# Power_Circuit.net
KiCad netlist of a schematic drawn in Altium Designer
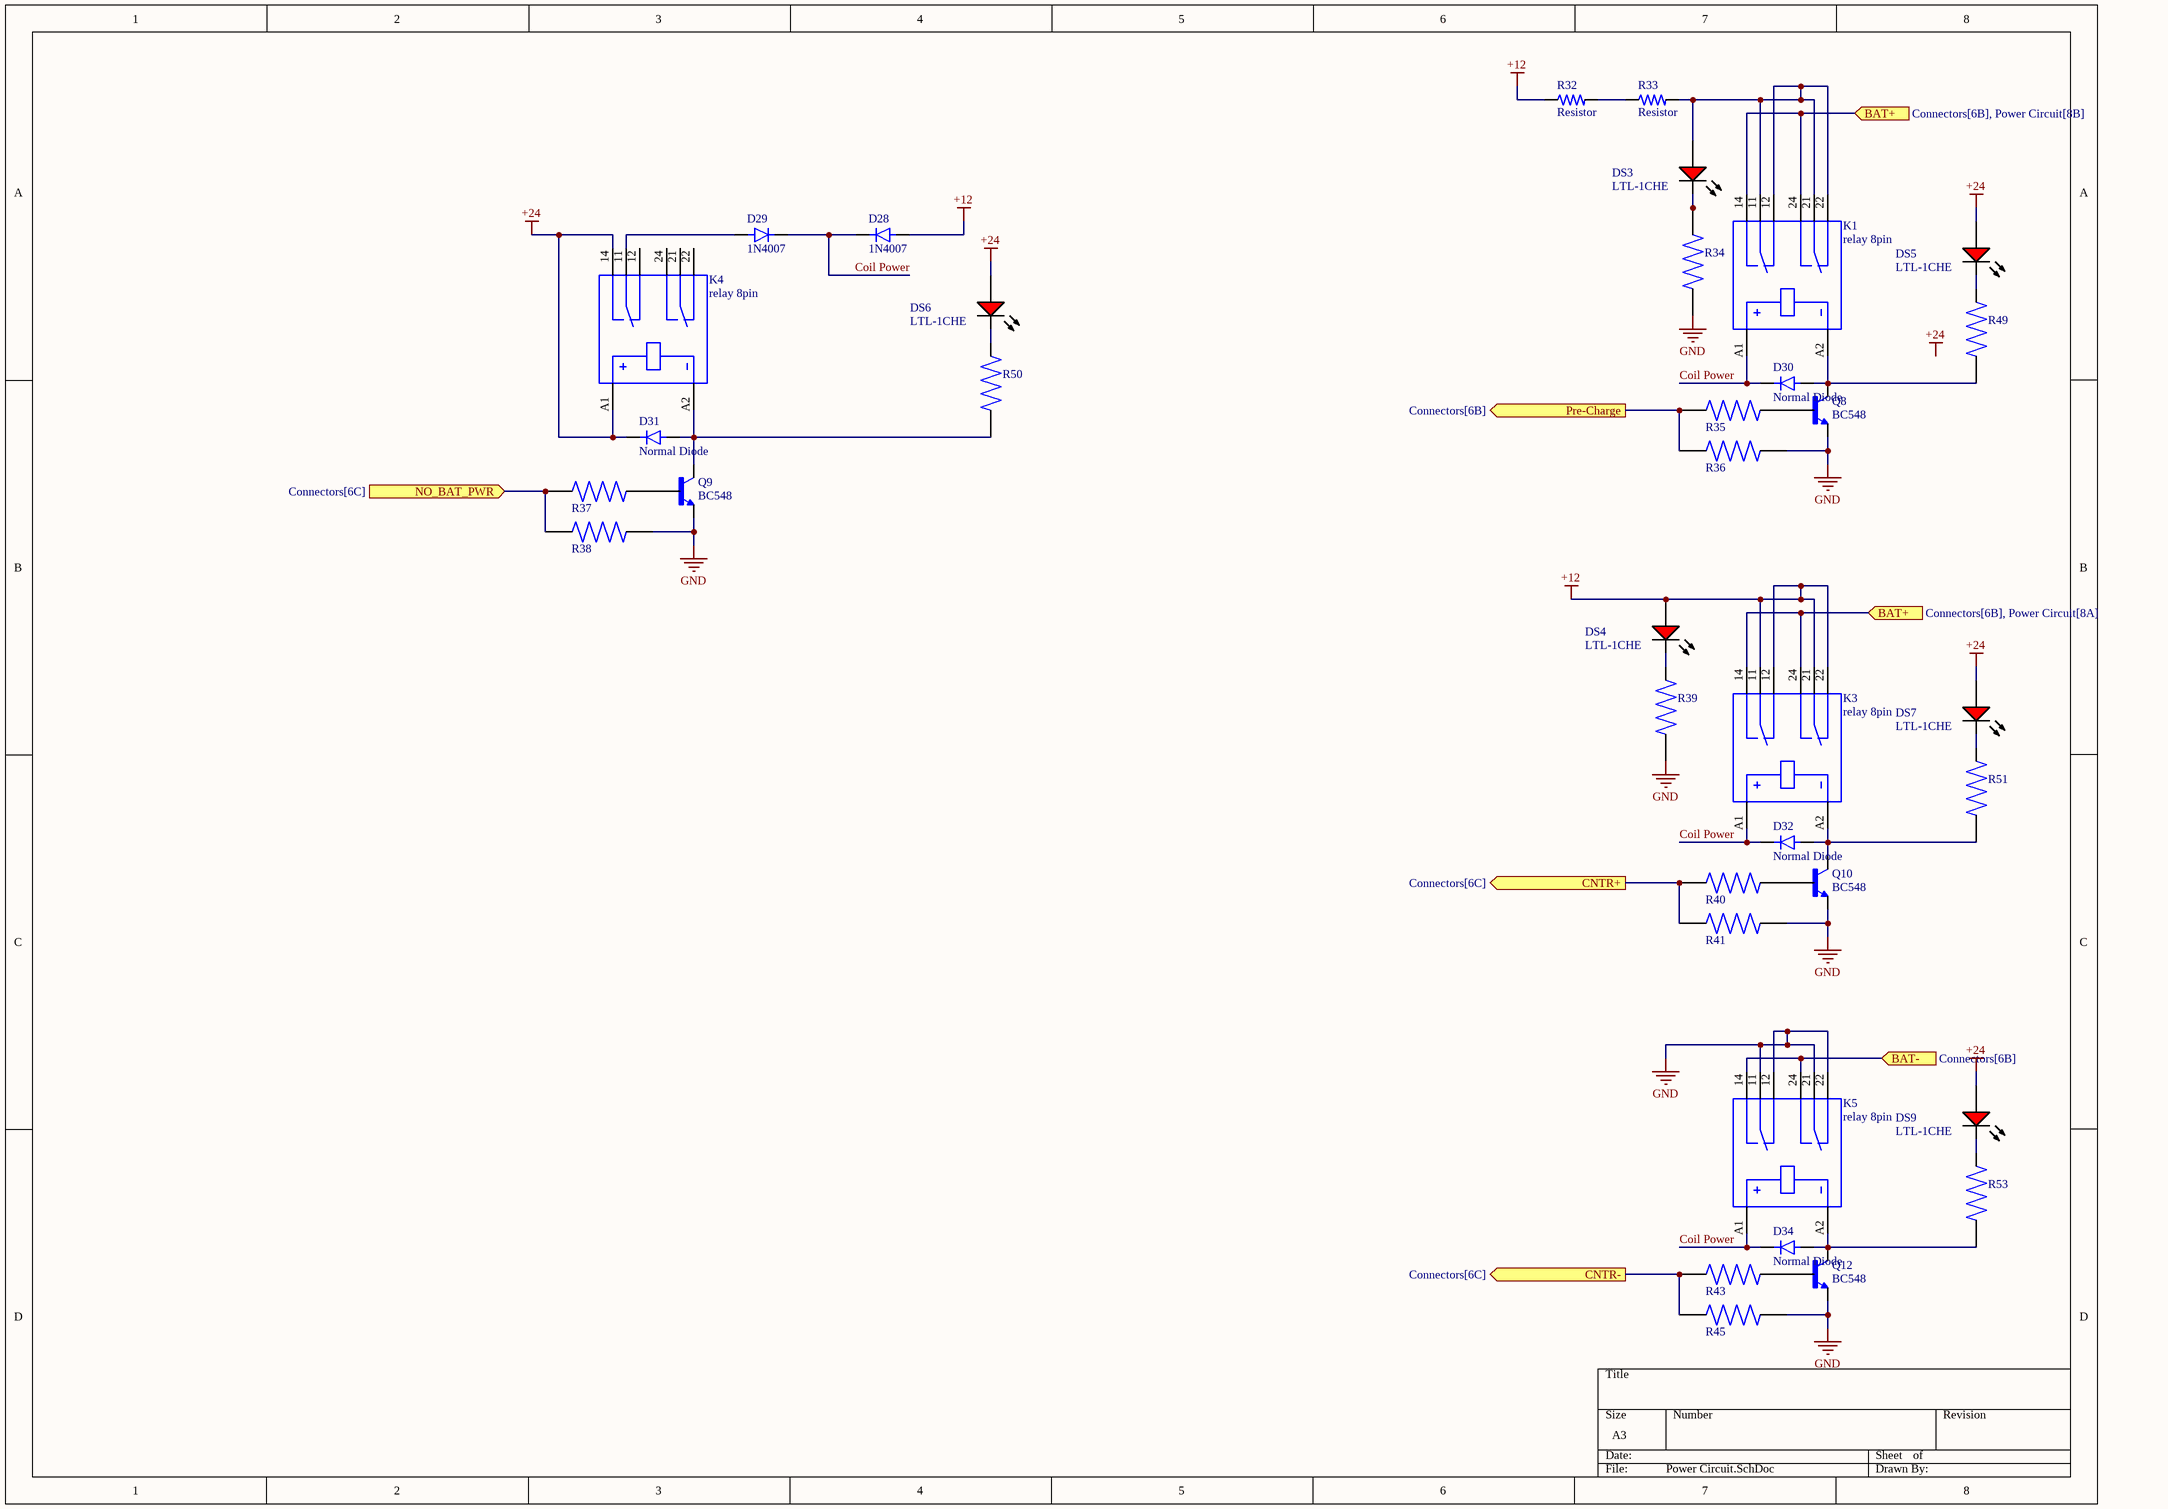
[diagram p0: Power Circuit.SchDoc]

(export (version "E")
  (design (tool "Eeschema 10.0.6"))
  (components
    (comp (ref "D28")
      (value "1N4007")
      (footprint "Common Trhough Hole")
      (fields (field (name "MF") "NTE Electronics, Inc."))
      (libsource (lib "Diodes Through Hole") (part "Normal Diode"))
    )
    (comp (ref "D29")
      (value "1N4007")
      (footprint "Common Trhough Hole")
      (fields (field (name "MF") "NTE Electronics, Inc."))
      (libsource (lib "Diodes Through Hole") (part "Normal Diode"))
    )
    (comp (ref "D30")
      (value "Normal Diode")
      (footprint "Common Trhough Hole")
      (fields (field (name "MF") "NTE Electronics, Inc.") (field (name "MP") "1N4007"))
      (libsource (lib "Diodes Through Hole") (part "Normal Diode"))
    )
    (comp (ref "D31")
      (value "Normal Diode")
      (footprint "Common Trhough Hole")
      (fields (field (name "MF") "NTE Electronics, Inc.") (field (name "MP") "1N4007"))
      (libsource (lib "Diodes Through Hole") (part "Normal Diode"))
    )
    (comp (ref "D32")
      (value "Normal Diode")
      (footprint "Common Trhough Hole")
      (fields (field (name "MF") "NTE Electronics, Inc.") (field (name "MP") "1N4007"))
      (libsource (lib "Diodes Through Hole") (part "Normal Diode"))
    )
    (comp (ref "D34")
      (value "Normal Diode")
      (footprint "Common Trhough Hole")
      (fields (field (name "MF") "NTE Electronics, Inc.") (field (name "MP") "1N4007"))
      (libsource (lib "Diodes Through Hole") (part "Normal Diode"))
    )
    (comp (ref "DS3")
      (value "LTL-1CHE")
      (footprint "LED3mm")
      (description "Radial LED, 12.6 mcd, 20 mA, 2 V, -55 to 100 degC, 2-Pin THD, RoHS, Bulk")
      (fields (field (name "TOLERANCE") "20%"))
      (libsource (lib "MySCH_Library") (part "RED_LED 3mm"))
    )
    (comp (ref "DS4")
      (value "LTL-1CHE")
      (footprint "LED3mm")
      (description "Radial LED, 12.6 mcd, 20 mA, 2 V, -55 to 100 degC, 2-Pin THD, RoHS, Bulk")
      (fields (field (name "TOLERANCE") "20%"))
      (libsource (lib "MySCH_Library") (part "RED_LED 3mm"))
    )
    (comp (ref "DS5")
      (value "LTL-1CHE")
      (footprint "LED3mm")
      (description "Radial LED, 12.6 mcd, 20 mA, 2 V, -55 to 100 degC, 2-Pin THD, RoHS, Bulk")
      (fields (field (name "TOLERANCE") "20%"))
      (libsource (lib "MySCH_Library") (part "RED_LED 3mm"))
    )
    (comp (ref "DS6")
      (value "LTL-1CHE")
      (footprint "LED3mm")
      (description "Radial LED, 12.6 mcd, 20 mA, 2 V, -55 to 100 degC, 2-Pin THD, RoHS, Bulk")
      (fields (field (name "TOLERANCE") "20%"))
      (libsource (lib "MySCH_Library") (part "RED_LED 3mm"))
    )
    (comp (ref "DS7")
      (value "LTL-1CHE")
      (footprint "LED3mm")
      (description "Radial LED, 12.6 mcd, 20 mA, 2 V, -55 to 100 degC, 2-Pin THD, RoHS, Bulk")
      (fields (field (name "TOLERANCE") "20%"))
      (libsource (lib "MySCH_Library") (part "RED_LED 3mm"))
    )
    (comp (ref "DS9")
      (value "LTL-1CHE")
      (footprint "LED3mm")
      (description "Radial LED, 12.6 mcd, 20 mA, 2 V, -55 to 100 degC, 2-Pin THD, RoHS, Bulk")
      (fields (field (name "TOLERANCE") "20%"))
      (libsource (lib "MySCH_Library") (part "RED_LED 3mm"))
    )
    (comp (ref "K1")
      (value "relay 8pin")
      (footprint "Relay socket 8pin")
      (description "General Purpose Relay DPDT _2 Form C_ 24VDC Coil Through Hole")
      (fields (field (name "MF") "TE Connectivity") (field (name "MP") "1-1393243-0"))
      (libsource (lib "MySCH_Library") (part "relay 8pin"))
    )
    (comp (ref "K3")
      (value "relay 8pin")
      (footprint "Relay socket 8pin")
      (description "General Purpose Relay DPDT _2 Form C_ 24VDC Coil Through Hole")
      (fields (field (name "MF") "TE Connectivity") (field (name "MP") "1-1393243-0"))
      (libsource (lib "MySCH_Library") (part "relay 8pin"))
    )
    (comp (ref "K4")
      (value "relay 8pin")
      (footprint "Relay socket 8pin")
      (description "General Purpose Relay DPDT _2 Form C_ 24VDC Coil Through Hole")
      (fields (field (name "MF") "TE Connectivity") (field (name "MP") "1-1393243-0"))
      (libsource (lib "MySCH_Library") (part "relay 8pin"))
    )
    (comp (ref "K5")
      (value "relay 8pin")
      (footprint "Relay socket 8pin")
      (description "General Purpose Relay DPDT _2 Form C_ 24VDC Coil Through Hole")
      (fields (field (name "MF") "TE Connectivity") (field (name "MP") "1-1393243-0"))
      (libsource (lib "MySCH_Library") (part "relay 8pin"))
    )
    (comp (ref "Q8")
      (value "BC548")
      (footprint "bc548")
      (description "Bipolar (BJT) Transistor NPN 30V 100mA 300MHz 500mW Through Hole TO-92-3")
      (fields (field (name "MF") "ON Semiconductor"))
      (libsource (lib "MySCH_Library") (part "BC548"))
    )
    (comp (ref "Q9")
      (value "BC548")
      (footprint "bc548")
      (description "Bipolar (BJT) Transistor NPN 30V 100mA 300MHz 500mW Through Hole TO-92-3")
      (fields (field (name "MF") "ON Semiconductor"))
      (libsource (lib "MySCH_Library") (part "BC548"))
    )
    (comp (ref "Q10")
      (value "BC548")
      (footprint "bc548")
      (description "Bipolar (BJT) Transistor NPN 30V 100mA 300MHz 500mW Through Hole TO-92-3")
      (fields (field (name "MF") "ON Semiconductor"))
      (libsource (lib "MySCH_Library") (part "BC548"))
    )
    (comp (ref "Q12")
      (value "BC548")
      (footprint "bc548")
      (description "Bipolar (BJT) Transistor NPN 30V 100mA 300MHz 500mW Through Hole TO-92-3")
      (fields (field (name "MF") "ON Semiconductor"))
      (libsource (lib "MySCH_Library") (part "BC548"))
    )
    (comp (ref "R32")
      (value "Resistor")
      (footprint "Resistor_Through Hole")
      (fields
        (field (name "MP") "2-2176053-0")
        (field (name "TOLERANCE") "1%")
        (field (name "MF") "TE Connectivity")
      )
      (libsource (lib "Resistors Through Hole") (part "Resistor"))
    )
    (comp (ref "R33")
      (value "Resistor")
      (footprint "Resistor_Through Hole")
      (fields
        (field (name "MP") "2-2176053-0")
        (field (name "TOLERANCE") "1%")
        (field (name "MF") "TE Connectivity")
      )
      (libsource (lib "Resistors Through Hole") (part "Resistor"))
    )
    (comp (ref "R34")
      (value "Resistor_Through Hole")
      (footprint "Resistor_Through Hole")
      (description "1.02 Ohms Â±1% 0.25W, 1/4W Through Hole Resistor Axial Metal Film")
      (fields (field (name "MP") "MFR-25FTE52-1R") (field (name "MF") "Yageo"))
      (libsource (lib "MySCH_Library") (part "Resistor_Through Hole"))
    )
    (comp (ref "R35")
      (value "Resistor_Through Hole")
      (footprint "Resistor_Through Hole")
      (description "1.02 Ohms Â±1% 0.25W, 1/4W Through Hole Resistor Axial Metal Film")
      (fields (field (name "MP") "MFR-25FTE52-1R") (field (name "MF") "Yageo"))
      (libsource (lib "MySCH_Library") (part "Resistor_Through Hole"))
    )
    (comp (ref "R36")
      (value "Resistor_Through Hole")
      (footprint "Resistor_Through Hole")
      (description "1.02 Ohms Â±1% 0.25W, 1/4W Through Hole Resistor Axial Metal Film")
      (fields (field (name "MP") "MFR-25FTE52-1R") (field (name "MF") "Yageo"))
      (libsource (lib "MySCH_Library") (part "Resistor_Through Hole"))
    )
    (comp (ref "R37")
      (value "Resistor_Through Hole")
      (footprint "Resistor_Through Hole")
      (description "1.02 Ohms Â±1% 0.25W, 1/4W Through Hole Resistor Axial Metal Film")
      (fields (field (name "MP") "MFR-25FTE52-1R") (field (name "MF") "Yageo"))
      (libsource (lib "MySCH_Library") (part "Resistor_Through Hole"))
    )
    (comp (ref "R38")
      (value "Resistor_Through Hole")
      (footprint "Resistor_Through Hole")
      (description "1.02 Ohms Â±1% 0.25W, 1/4W Through Hole Resistor Axial Metal Film")
      (fields (field (name "MP") "MFR-25FTE52-1R") (field (name "MF") "Yageo"))
      (libsource (lib "MySCH_Library") (part "Resistor_Through Hole"))
    )
    (comp (ref "R39")
      (value "Resistor_Through Hole")
      (footprint "Resistor_Through Hole")
      (description "1.02 Ohms Â±1% 0.25W, 1/4W Through Hole Resistor Axial Metal Film")
      (fields (field (name "MP") "MFR-25FTE52-1R") (field (name "MF") "Yageo"))
      (libsource (lib "MySCH_Library") (part "Resistor_Through Hole"))
    )
    (comp (ref "R40")
      (value "Resistor_Through Hole")
      (footprint "Resistor_Through Hole")
      (description "1.02 Ohms Â±1% 0.25W, 1/4W Through Hole Resistor Axial Metal Film")
      (fields (field (name "MP") "MFR-25FTE52-1R") (field (name "MF") "Yageo"))
      (libsource (lib "MySCH_Library") (part "Resistor_Through Hole"))
    )
    (comp (ref "R41")
      (value "Resistor_Through Hole")
      (footprint "Resistor_Through Hole")
      (description "1.02 Ohms Â±1% 0.25W, 1/4W Through Hole Resistor Axial Metal Film")
      (fields (field (name "MP") "MFR-25FTE52-1R") (field (name "MF") "Yageo"))
      (libsource (lib "MySCH_Library") (part "Resistor_Through Hole"))
    )
    (comp (ref "R43")
      (value "Resistor_Through Hole")
      (footprint "Resistor_Through Hole")
      (description "1.02 Ohms Â±1% 0.25W, 1/4W Through Hole Resistor Axial Metal Film")
      (fields (field (name "MP") "MFR-25FTE52-1R") (field (name "MF") "Yageo"))
      (libsource (lib "MySCH_Library") (part "Resistor_Through Hole"))
    )
    (comp (ref "R45")
      (value "Resistor_Through Hole")
      (footprint "Resistor_Through Hole")
      (description "1.02 Ohms Â±1% 0.25W, 1/4W Through Hole Resistor Axial Metal Film")
      (fields (field (name "MP") "MFR-25FTE52-1R") (field (name "MF") "Yageo"))
      (libsource (lib "MySCH_Library") (part "Resistor_Through Hole"))
    )
    (comp (ref "R49")
      (value "Resistor_Through Hole")
      (footprint "Resistor_Through Hole")
      (description "1.02 Ohms Â±1% 0.25W, 1/4W Through Hole Resistor Axial Metal Film")
      (fields (field (name "MP") "MFR-25FTE52-1R") (field (name "MF") "Yageo"))
      (libsource (lib "MySCH_Library") (part "Resistor_Through Hole"))
    )
    (comp (ref "R50")
      (value "Resistor_Through Hole")
      (footprint "Resistor_Through Hole")
      (description "1.02 Ohms Â±1% 0.25W, 1/4W Through Hole Resistor Axial Metal Film")
      (fields (field (name "MP") "MFR-25FTE52-1R") (field (name "MF") "Yageo"))
      (libsource (lib "MySCH_Library") (part "Resistor_Through Hole"))
    )
    (comp (ref "R51")
      (value "Resistor_Through Hole")
      (footprint "Resistor_Through Hole")
      (description "1.02 Ohms Â±1% 0.25W, 1/4W Through Hole Resistor Axial Metal Film")
      (fields (field (name "MP") "MFR-25FTE52-1R") (field (name "MF") "Yageo"))
      (libsource (lib "MySCH_Library") (part "Resistor_Through Hole"))
    )
    (comp (ref "R53")
      (value "Resistor_Through Hole")
      (footprint "Resistor_Through Hole")
      (description "1.02 Ohms Â±1% 0.25W, 1/4W Through Hole Resistor Axial Metal Film")
      (fields (field (name "MP") "MFR-25FTE52-1R") (field (name "MF") "Yageo"))
      (libsource (lib "MySCH_Library") (part "Resistor_Through Hole"))
    )
  )
  (nets
    (net (code "1") (name "+12") (class "Default")
      (node (ref "D28") (pin "2") (pinfunction "A_2") (pintype "passive"))
      (node (ref "DS4") (pin "1") (pinfunction "A_1") (pintype "passive"))
      (node (ref "K3") (pin "11") (pinfunction "6_11") (pintype "passive"))
      (node (ref "K3") (pin "12") (pinfunction "7_12") (pintype "passive"))
      (node (ref "K3") (pin "21") (pinfunction "3_21") (pintype "passive"))
      (node (ref "K3") (pin "22") (pinfunction "2_22") (pintype "passive"))
      (node (ref "R32") (pin "1") (pinfunction "1_1") (pintype "passive"))
    )
    (net (code "2") (name "+24") (class "Default")
      (node (ref "D31") (pin "1") (pinfunction "K_1") (pintype "passive"))
      (node (ref "DS5") (pin "1") (pinfunction "A_1") (pintype "passive"))
      (node (ref "DS6") (pin "1") (pinfunction "A_1") (pintype "passive"))
      (node (ref "DS7") (pin "1") (pinfunction "A_1") (pintype "passive"))
      (node (ref "DS9") (pin "1") (pinfunction "A_1") (pintype "passive"))
      (node (ref "K4") (pin "14") (pinfunction "5_14") (pintype "passive"))
      (node (ref "K4") (pin "A1") (pinfunction "1_A1") (pintype "passive"))
    )
    (net (code "3") (name "/BAT+") (class "Default")
      (node (ref "K1") (pin "14") (pinfunction "5_14") (pintype "passive"))
      (node (ref "K1") (pin "24") (pinfunction "4_24") (pintype "passive"))
      (node (ref "K3") (pin "14") (pinfunction "5_14") (pintype "passive"))
      (node (ref "K3") (pin "24") (pinfunction "4_24") (pintype "passive"))
    )
    (net (code "4") (name "/BAT-") (class "Default")
      (node (ref "K5") (pin "14") (pinfunction "5_14") (pintype "passive"))
      (node (ref "K5") (pin "24") (pinfunction "4_24") (pintype "passive"))
    )
    (net (code "5") (name "/CNTR+") (class "Default")
      (node (ref "R40") (pin "2") (pinfunction "2_2") (pintype "passive"))
      (node (ref "R41") (pin "2") (pinfunction "2_2") (pintype "passive"))
    )
    (net (code "6") (name "/CNTR-") (class "Default")
      (node (ref "R43") (pin "2") (pinfunction "2_2") (pintype "passive"))
      (node (ref "R45") (pin "2") (pinfunction "2_2") (pintype "passive"))
    )
    (net (code "7") (name "/Coil Power") (class "Default")
      (node (ref "D28") (pin "1") (pinfunction "K_1") (pintype "passive"))
      (node (ref "D29") (pin "1") (pinfunction "K_1") (pintype "passive"))
      (node (ref "D30") (pin "1") (pinfunction "K_1") (pintype "passive"))
      (node (ref "D32") (pin "1") (pinfunction "K_1") (pintype "passive"))
      (node (ref "D34") (pin "1") (pinfunction "K_1") (pintype "passive"))
      (node (ref "K1") (pin "A1") (pinfunction "1_A1") (pintype "passive"))
      (node (ref "K3") (pin "A1") (pinfunction "1_A1") (pintype "passive"))
      (node (ref "K5") (pin "A1") (pinfunction "1_A1") (pintype "passive"))
    )
    (net (code "8") (name "/NO_BAT_PWR") (class "Default")
      (node (ref "R37") (pin "2") (pinfunction "2_2") (pintype "passive"))
      (node (ref "R38") (pin "2") (pinfunction "2_2") (pintype "passive"))
    )
    (net (code "9") (name "/Pre-Charge") (class "Default")
      (node (ref "R35") (pin "2") (pinfunction "2_2") (pintype "passive"))
      (node (ref "R36") (pin "2") (pinfunction "2_2") (pintype "passive"))
    )
    (net (code "10") (name "GND") (class "Default")
      (node (ref "K5") (pin "11") (pinfunction "6_11") (pintype "passive"))
      (node (ref "K5") (pin "12") (pinfunction "7_12") (pintype "passive"))
      (node (ref "K5") (pin "21") (pinfunction "3_21") (pintype "passive"))
      (node (ref "K5") (pin "22") (pinfunction "2_22") (pintype "passive"))
      (node (ref "Q10") (pin "3") (pinfunction "E_3") (pintype "passive"))
      (node (ref "Q12") (pin "3") (pinfunction "E_3") (pintype "passive"))
      (node (ref "Q8") (pin "3") (pinfunction "E_3") (pintype "passive"))
      (node (ref "Q9") (pin "3") (pinfunction "E_3") (pintype "passive"))
      (node (ref "R34") (pin "2") (pinfunction "2_2") (pintype "passive"))
      (node (ref "R36") (pin "1") (pinfunction "1_1") (pintype "passive"))
      (node (ref "R38") (pin "1") (pinfunction "1_1") (pintype "passive"))
      (node (ref "R39") (pin "2") (pinfunction "2_2") (pintype "passive"))
      (node (ref "R41") (pin "1") (pinfunction "1_1") (pintype "passive"))
      (node (ref "R45") (pin "1") (pinfunction "1_1") (pintype "passive"))
    )
    (net (code "11") (name "Net-(D29-A)") (class "Default")
      (node (ref "D29") (pin "2") (pinfunction "A_2") (pintype "passive"))
      (node (ref "K4") (pin "11") (pinfunction "6_11") (pintype "passive"))
    )
    (net (code "12") (name "Net-(D30-A)") (class "Default")
      (node (ref "D30") (pin "2") (pinfunction "A_2") (pintype "passive"))
      (node (ref "K1") (pin "A2") (pinfunction "8_A2") (pintype "passive"))
      (node (ref "Q8") (pin "1") (pinfunction "C_1") (pintype "passive"))
      (node (ref "R49") (pin "2") (pinfunction "2_2") (pintype "passive"))
    )
    (net (code "13") (name "Net-(D31-A)") (class "Default")
      (node (ref "D31") (pin "2") (pinfunction "A_2") (pintype "passive"))
      (node (ref "K4") (pin "A2") (pinfunction "8_A2") (pintype "passive"))
      (node (ref "Q9") (pin "1") (pinfunction "C_1") (pintype "passive"))
      (node (ref "R50") (pin "2") (pinfunction "2_2") (pintype "passive"))
    )
    (net (code "14") (name "Net-(D32-A)") (class "Default")
      (node (ref "D32") (pin "2") (pinfunction "A_2") (pintype "passive"))
      (node (ref "K3") (pin "A2") (pinfunction "8_A2") (pintype "passive"))
      (node (ref "Q10") (pin "1") (pinfunction "C_1") (pintype "passive"))
      (node (ref "R51") (pin "2") (pinfunction "2_2") (pintype "passive"))
    )
    (net (code "15") (name "Net-(D34-A)") (class "Default")
      (node (ref "D34") (pin "2") (pinfunction "A_2") (pintype "passive"))
      (node (ref "K5") (pin "A2") (pinfunction "8_A2") (pintype "passive"))
      (node (ref "Q12") (pin "1") (pinfunction "C_1") (pintype "passive"))
      (node (ref "R53") (pin "2") (pinfunction "2_2") (pintype "passive"))
    )
    (net (code "16") (name "Net-(DS3-A)") (class "Default")
      (node (ref "DS3") (pin "1") (pinfunction "A_1") (pintype "passive"))
      (node (ref "K1") (pin "11") (pinfunction "6_11") (pintype "passive"))
      (node (ref "K1") (pin "12") (pinfunction "7_12") (pintype "passive"))
      (node (ref "K1") (pin "21") (pinfunction "3_21") (pintype "passive"))
      (node (ref "K1") (pin "22") (pinfunction "2_22") (pintype "passive"))
      (node (ref "R33") (pin "2") (pinfunction "2_2") (pintype "passive"))
    )
    (net (code "17") (name "Net-(DS3-K)") (class "Default")
      (node (ref "DS3") (pin "2") (pinfunction "K_2") (pintype "passive"))
      (node (ref "R34") (pin "1") (pinfunction "1_1") (pintype "passive"))
    )
    (net (code "18") (name "Net-(DS4-K)") (class "Default")
      (node (ref "DS4") (pin "2") (pinfunction "K_2") (pintype "passive"))
      (node (ref "R39") (pin "1") (pinfunction "1_1") (pintype "passive"))
    )
    (net (code "19") (name "Net-(DS5-K)") (class "Default")
      (node (ref "DS5") (pin "2") (pinfunction "K_2") (pintype "passive"))
      (node (ref "R49") (pin "1") (pinfunction "1_1") (pintype "passive"))
    )
    (net (code "20") (name "Net-(DS6-K)") (class "Default")
      (node (ref "DS6") (pin "2") (pinfunction "K_2") (pintype "passive"))
      (node (ref "R50") (pin "1") (pinfunction "1_1") (pintype "passive"))
    )
    (net (code "21") (name "Net-(DS7-K)") (class "Default")
      (node (ref "DS7") (pin "2") (pinfunction "K_2") (pintype "passive"))
      (node (ref "R51") (pin "1") (pinfunction "1_1") (pintype "passive"))
    )
    (net (code "22") (name "Net-(DS9-K)") (class "Default")
      (node (ref "DS9") (pin "2") (pinfunction "K_2") (pintype "passive"))
      (node (ref "R53") (pin "1") (pinfunction "1_1") (pintype "passive"))
    )
    (net (code "23") (name "Net-(Q8-B)") (class "Default")
      (node (ref "Q8") (pin "2") (pinfunction "B_2") (pintype "passive"))
      (node (ref "R35") (pin "1") (pinfunction "1_1") (pintype "passive"))
    )
    (net (code "24") (name "Net-(Q9-B)") (class "Default")
      (node (ref "Q9") (pin "2") (pinfunction "B_2") (pintype "passive"))
      (node (ref "R37") (pin "1") (pinfunction "1_1") (pintype "passive"))
    )
    (net (code "25") (name "Net-(Q10-B)") (class "Default")
      (node (ref "Q10") (pin "2") (pinfunction "B_2") (pintype "passive"))
      (node (ref "R40") (pin "1") (pinfunction "1_1") (pintype "passive"))
    )
    (net (code "26") (name "Net-(Q12-B)") (class "Default")
      (node (ref "Q12") (pin "2") (pinfunction "B_2") (pintype "passive"))
      (node (ref "R43") (pin "1") (pinfunction "1_1") (pintype "passive"))
    )
    (net (code "27") (name "Net-(R32-Pad2)") (class "Default")
      (node (ref "R32") (pin "2") (pinfunction "2_2") (pintype "passive"))
      (node (ref "R33") (pin "1") (pinfunction "1_1") (pintype "passive"))
    )
    (net (code "28") (name "unconnected-(K4-2-Pad22)") (class "Default")
      (node (ref "K4") (pin "22") (pinfunction "2_22") (pintype "passive"))
    )
    (net (code "29") (name "unconnected-(K4-3-Pad21)") (class "Default")
      (node (ref "K4") (pin "21") (pinfunction "3_21") (pintype "passive"))
    )
    (net (code "30") (name "unconnected-(K4-4-Pad24)") (class "Default")
      (node (ref "K4") (pin "24") (pinfunction "4_24") (pintype "passive"))
    )
    (net (code "31") (name "unconnected-(K4-7-Pad12)") (class "Default")
      (node (ref "K4") (pin "12") (pinfunction "7_12") (pintype "passive"))
    )
  )
)
